# TorpedoSOM_ReceptorS.net
KiCad netlist of a schematic drawn in Altium Designer
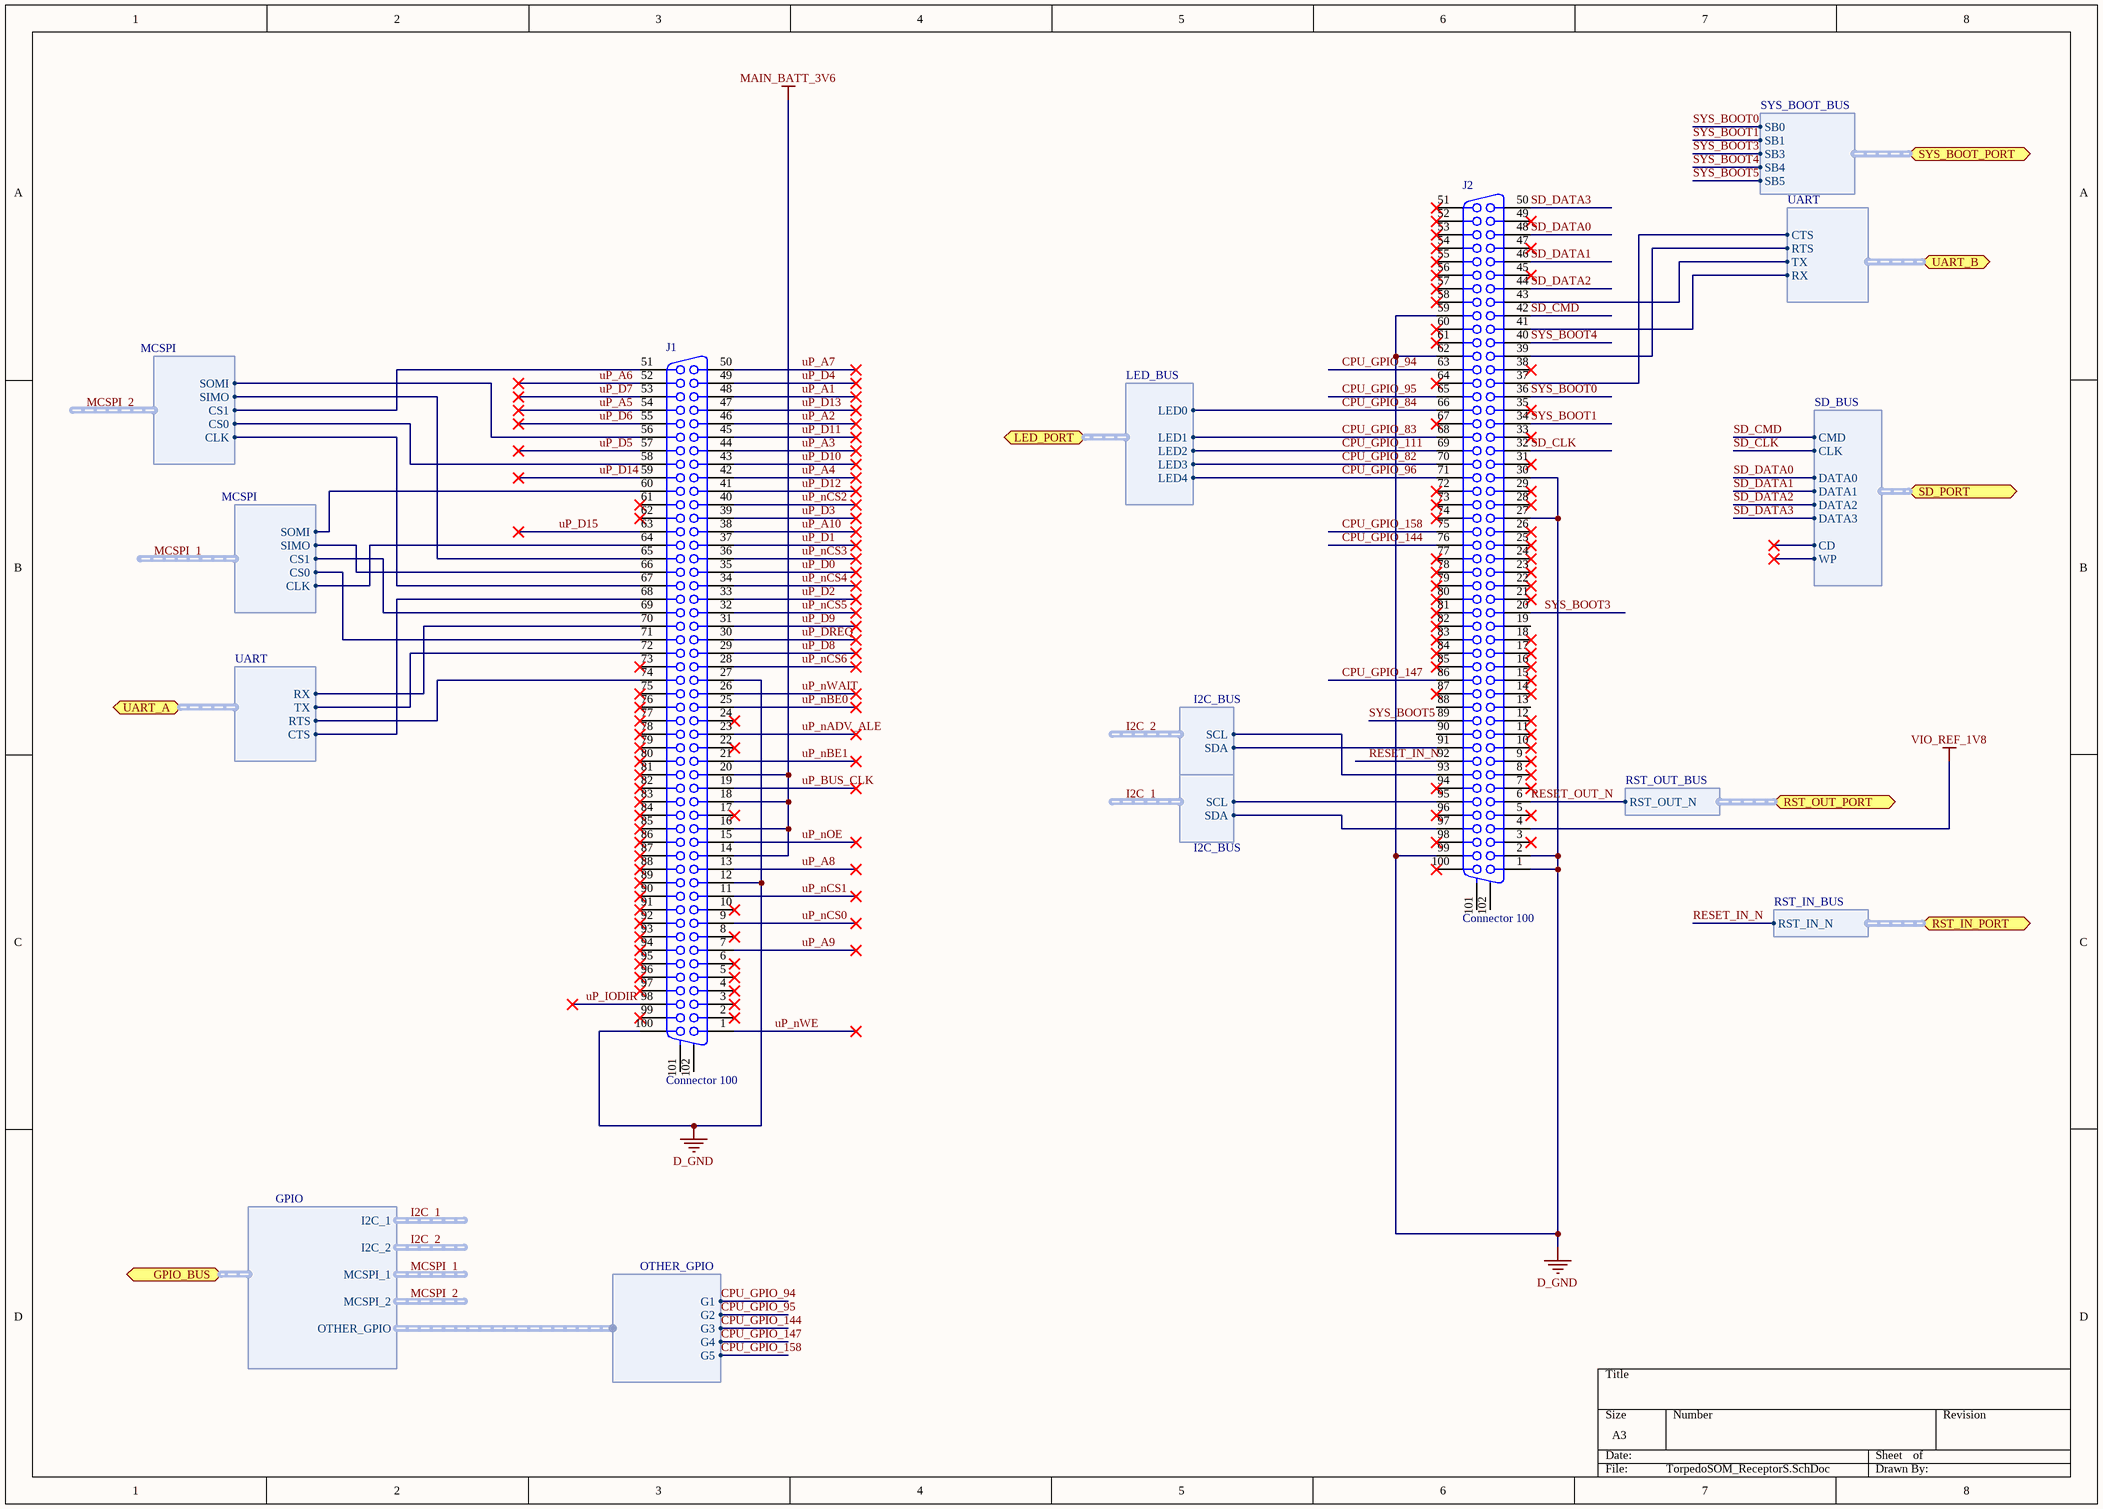
[diagram p0: TorpedoSOM_ReceptorS.SchDoc]

(export (version "E")
  (design (tool "Eeschema 10.0.6"))
  (components
    (comp (ref "J1")
      (value "Connector 100")
      (footprint "SOP127P600-8N_100PinConnRecptr_Hirose:SOP127P600-8N_100PinConnRecptr_Hirose")
      (description "Receptacle Header Assemby")
      (fields (field (name "PUBLISHER") "Altium Limited"))
      (libsource (lib "Miscellaneous Connectors") (part "Connector 100"))
    )
    (comp (ref "J2")
      (value "Connector 100")
      (footprint "SOP127P600-8N_100PinConnRecptr_Hirose:SOP127P600-8N_100PinConnRecptr_Hirose")
      (description "Receptacle Header Assemby")
      (fields (field (name "PUBLISHER") "Altium Limited"))
      (libsource (lib "Miscellaneous Connectors") (part "Connector 100"))
    )
  )
  (nets
    (net (code "17") (name "/CPU_GPIO_82") (class "Default")
      (node (ref "J2") (pin "70") (pinfunction "70_70") (pintype "passive"))
    )
    (net (code "18") (name "/CPU_GPIO_83") (class "Default")
      (node (ref "J2") (pin "68") (pinfunction "68_68") (pintype "passive"))
    )
    (net (code "19") (name "/CPU_GPIO_84") (class "Default")
      (node (ref "J2") (pin "66") (pinfunction "66_66") (pintype "passive"))
    )
    (net (code "20") (name "/CPU_GPIO_94") (class "Default")
      (node (ref "J2") (pin "63") (pinfunction "63_63") (pintype "passive"))
    )
    (net (code "21") (name "/CPU_GPIO_95") (class "Default")
      (node (ref "J2") (pin "65") (pinfunction "65_65") (pintype "passive"))
    )
    (net (code "22") (name "/CPU_GPIO_96") (class "Default")
      (node (ref "J2") (pin "71") (pinfunction "71_71") (pintype "passive"))
    )
    (net (code "23") (name "/CPU_GPIO_111") (class "Default")
      (node (ref "J2") (pin "69") (pinfunction "69_69") (pintype "passive"))
    )
    (net (code "24") (name "/CPU_GPIO_144") (class "Default")
      (node (ref "J2") (pin "76") (pinfunction "76_76") (pintype "passive"))
    )
    (net (code "25") (name "/CPU_GPIO_147") (class "Default")
      (node (ref "J2") (pin "86") (pinfunction "86_86") (pintype "passive"))
    )
    (net (code "26") (name "/CPU_GPIO_158") (class "Default")
      (node (ref "J2") (pin "75") (pinfunction "75_75") (pintype "passive"))
    )
    (net (code "32") (name "/RESET_IN_N") (class "Default")
      (node (ref "J2") (pin "92") (pinfunction "92_92") (pintype "passive"))
    )
    (net (code "33") (name "/RESET_OUT_N") (class "Default")
      (node (ref "J2") (pin "6") (pinfunction "6_6") (pintype "passive"))
    )
    (net (code "34") (name "/SD_CLK") (class "Default")
      (node (ref "J2") (pin "32") (pinfunction "32_32") (pintype "passive"))
    )
    (net (code "35") (name "/SD_CMD") (class "Default")
      (node (ref "J2") (pin "42") (pinfunction "42_42") (pintype "passive"))
    )
    (net (code "36") (name "/SD_DATA0") (class "Default")
      (node (ref "J2") (pin "48") (pinfunction "48_48") (pintype "passive"))
    )
    (net (code "37") (name "/SD_DATA1") (class "Default")
      (node (ref "J2") (pin "46") (pinfunction "46_46") (pintype "passive"))
    )
    (net (code "38") (name "/SD_DATA2") (class "Default")
      (node (ref "J2") (pin "44") (pinfunction "44_44") (pintype "passive"))
    )
    (net (code "39") (name "/SD_DATA3") (class "Default")
      (node (ref "J2") (pin "50") (pinfunction "50_50") (pintype "passive"))
    )
    (net (code "40") (name "/SYS_BOOT0") (class "Default")
      (node (ref "J2") (pin "36") (pinfunction "36_36") (pintype "passive"))
    )
    (net (code "41") (name "/SYS_BOOT1") (class "Default")
      (node (ref "J2") (pin "34") (pinfunction "34_34") (pintype "passive"))
    )
    (net (code "42") (name "/SYS_BOOT3") (class "Default")
      (node (ref "J2") (pin "20") (pinfunction "20_20") (pintype "passive"))
    )
    (net (code "43") (name "/SYS_BOOT4") (class "Default")
      (node (ref "J2") (pin "40") (pinfunction "40_40") (pintype "passive"))
    )
    (net (code "44") (name "/SYS_BOOT5") (class "Default")
      (node (ref "J2") (pin "89") (pinfunction "89_89") (pintype "passive"))
    )
    (net (code "45") (name "/uP_A1") (class "Default")
      (node (ref "J1") (pin "48") (pinfunction "48_48") (pintype "passive+no_connect"))
    )
    (net (code "46") (name "/uP_A2") (class "Default")
      (node (ref "J1") (pin "46") (pinfunction "46_46") (pintype "passive+no_connect"))
    )
    (net (code "47") (name "/uP_A3") (class "Default")
      (node (ref "J1") (pin "44") (pinfunction "44_44") (pintype "passive+no_connect"))
    )
    (net (code "48") (name "/uP_A4") (class "Default")
      (node (ref "J1") (pin "42") (pinfunction "42_42") (pintype "passive+no_connect"))
    )
    (net (code "49") (name "/uP_A5") (class "Default")
      (node (ref "J1") (pin "54") (pinfunction "54_54") (pintype "passive+no_connect"))
    )
    (net (code "50") (name "/uP_A6") (class "Default")
      (node (ref "J1") (pin "52") (pinfunction "52_52") (pintype "passive+no_connect"))
    )
    (net (code "51") (name "/uP_A7") (class "Default")
      (node (ref "J1") (pin "50") (pinfunction "50_50") (pintype "passive+no_connect"))
    )
    (net (code "52") (name "/uP_A8") (class "Default")
      (node (ref "J1") (pin "13") (pinfunction "13_13") (pintype "passive+no_connect"))
    )
    (net (code "53") (name "/uP_A9") (class "Default")
      (node (ref "J1") (pin "7") (pinfunction "7_7") (pintype "passive+no_connect"))
    )
    (net (code "54") (name "/uP_A10") (class "Default")
      (node (ref "J1") (pin "38") (pinfunction "38_38") (pintype "passive+no_connect"))
    )
    (net (code "55") (name "/uP_BUS_CLK") (class "Default")
      (node (ref "J1") (pin "19") (pinfunction "19_19") (pintype "passive+no_connect"))
    )
    (net (code "56") (name "/uP_D0") (class "Default")
      (node (ref "J1") (pin "35") (pinfunction "35_35") (pintype "passive+no_connect"))
    )
    (net (code "57") (name "/uP_D1") (class "Default")
      (node (ref "J1") (pin "37") (pinfunction "37_37") (pintype "passive+no_connect"))
    )
    (net (code "58") (name "/uP_D2") (class "Default")
      (node (ref "J1") (pin "33") (pinfunction "33_33") (pintype "passive+no_connect"))
    )
    (net (code "59") (name "/uP_D3") (class "Default")
      (node (ref "J1") (pin "39") (pinfunction "39_39") (pintype "passive+no_connect"))
    )
    (net (code "60") (name "/uP_D4") (class "Default")
      (node (ref "J1") (pin "49") (pinfunction "49_49") (pintype "passive+no_connect"))
    )
    (net (code "61") (name "/uP_D5") (class "Default")
      (node (ref "J1") (pin "57") (pinfunction "57_57") (pintype "passive+no_connect"))
    )
    (net (code "62") (name "/uP_D6") (class "Default")
      (node (ref "J1") (pin "55") (pinfunction "55_55") (pintype "passive+no_connect"))
    )
    (net (code "63") (name "/uP_D7") (class "Default")
      (node (ref "J1") (pin "53") (pinfunction "53_53") (pintype "passive+no_connect"))
    )
    (net (code "64") (name "/uP_D8") (class "Default")
      (node (ref "J1") (pin "29") (pinfunction "29_29") (pintype "passive+no_connect"))
    )
    (net (code "65") (name "/uP_D9") (class "Default")
      (node (ref "J1") (pin "31") (pinfunction "31_31") (pintype "passive+no_connect"))
    )
    (net (code "66") (name "/uP_D10") (class "Default")
      (node (ref "J1") (pin "43") (pinfunction "43_43") (pintype "passive+no_connect"))
    )
    (net (code "67") (name "/uP_D11") (class "Default")
      (node (ref "J1") (pin "45") (pinfunction "45_45") (pintype "passive+no_connect"))
    )
    (net (code "68") (name "/uP_D12") (class "Default")
      (node (ref "J1") (pin "41") (pinfunction "41_41") (pintype "passive+no_connect"))
    )
    (net (code "69") (name "/uP_D13") (class "Default")
      (node (ref "J1") (pin "47") (pinfunction "47_47") (pintype "passive+no_connect"))
    )
    (net (code "70") (name "/uP_D14") (class "Default")
      (node (ref "J1") (pin "59") (pinfunction "59_59") (pintype "passive+no_connect"))
    )
    (net (code "71") (name "/uP_D15") (class "Default")
      (node (ref "J1") (pin "63") (pinfunction "63_63") (pintype "passive+no_connect"))
    )
    (net (code "72") (name "/uP_DREQ") (class "Default")
      (node (ref "J1") (pin "30") (pinfunction "30_30") (pintype "passive+no_connect"))
    )
    (net (code "73") (name "/uP_IODIR") (class "Default")
      (node (ref "J1") (pin "98") (pinfunction "98_98") (pintype "passive+no_connect"))
    )
    (net (code "74") (name "/uP_nADV_ALE") (class "Default")
      (node (ref "J1") (pin "23") (pinfunction "23_23") (pintype "passive+no_connect"))
    )
    (net (code "75") (name "/uP_nBE0") (class "Default")
      (node (ref "J1") (pin "25") (pinfunction "25_25") (pintype "passive+no_connect"))
    )
    (net (code "76") (name "/uP_nBE1") (class "Default")
      (node (ref "J1") (pin "21") (pinfunction "21_21") (pintype "passive+no_connect"))
    )
    (net (code "77") (name "/uP_nCS0") (class "Default")
      (node (ref "J1") (pin "9") (pinfunction "9_9") (pintype "passive+no_connect"))
    )
    (net (code "78") (name "/uP_nCS1") (class "Default")
      (node (ref "J1") (pin "11") (pinfunction "11_11") (pintype "passive+no_connect"))
    )
    (net (code "79") (name "/uP_nCS2") (class "Default")
      (node (ref "J1") (pin "40") (pinfunction "40_40") (pintype "passive+no_connect"))
    )
    (net (code "80") (name "/uP_nCS3") (class "Default")
      (node (ref "J1") (pin "36") (pinfunction "36_36") (pintype "passive+no_connect"))
    )
    (net (code "81") (name "/uP_nCS4") (class "Default")
      (node (ref "J1") (pin "34") (pinfunction "34_34") (pintype "passive+no_connect"))
    )
    (net (code "82") (name "/uP_nCS5") (class "Default")
      (node (ref "J1") (pin "32") (pinfunction "32_32") (pintype "passive+no_connect"))
    )
    (net (code "83") (name "/uP_nCS6") (class "Default")
      (node (ref "J1") (pin "28") (pinfunction "28_28") (pintype "passive+no_connect"))
    )
    (net (code "84") (name "/uP_nOE") (class "Default")
      (node (ref "J1") (pin "15") (pinfunction "15_15") (pintype "passive+no_connect"))
    )
    (net (code "85") (name "/uP_nWAIT") (class "Default")
      (node (ref "J1") (pin "26") (pinfunction "26_26") (pintype "passive+no_connect"))
    )
    (net (code "86") (name "/uP_nWE") (class "Default")
      (node (ref "J1") (pin "1") (pinfunction "1_1") (pintype "passive+no_connect"))
    )
    (net (code "98") (name "D_GND") (class "Default")
      (node (ref "J1") (pin "100") (pinfunction "100_100") (pintype "passive"))
      (node (ref "J1") (pin "12") (pinfunction "12_12") (pintype "passive"))
      (node (ref "J1") (pin "27") (pinfunction "27_27") (pintype "passive"))
      (node (ref "J2") (pin "1") (pinfunction "1_1") (pintype "passive"))
      (node (ref "J2") (pin "2") (pinfunction "2_2") (pintype "passive"))
      (node (ref "J2") (pin "27") (pinfunction "27_27") (pintype "passive"))
      (node (ref "J2") (pin "30") (pinfunction "30_30") (pintype "passive"))
      (node (ref "J2") (pin "59") (pinfunction "59_59") (pintype "passive"))
      (node (ref "J2") (pin "62") (pinfunction "62_62") (pintype "passive"))
      (node (ref "J2") (pin "99") (pinfunction "99_99") (pintype "passive"))
    )
    (net (code "99") (name "MAIN_BATT_3V6") (class "Default")
      (node (ref "J1") (pin "14") (pinfunction "14_14") (pintype "passive"))
      (node (ref "J1") (pin "16") (pinfunction "16_16") (pintype "passive"))
      (node (ref "J1") (pin "18") (pinfunction "18_18") (pintype "passive"))
      (node (ref "J1") (pin "20") (pinfunction "20_20") (pintype "passive"))
    )
    (net (code "100") (name "VIO_REF_1V8") (class "Default")
      (node (ref "J2") (pin "4") (pinfunction "4_4") (pintype "passive"))
    )
    (net (code "101") (name "unconnected-(J1-MH1-Pad101)") (class "Default")
      (node (ref "J1") (pin "101") (pinfunction "MH1_101") (pintype "passive"))
    )
    (net (code "102") (name "unconnected-(J1-MH2-Pad102)") (class "Default")
      (node (ref "J1") (pin "102") (pinfunction "MH2_102") (pintype "passive"))
    )
    (net (code "103") (name "unconnected-(J1-Pad2)") (class "Default")
      (node (ref "J1") (pin "2") (pinfunction "2_2") (pintype "passive+no_connect"))
    )
    (net (code "104") (name "unconnected-(J1-Pad3)") (class "Default")
      (node (ref "J1") (pin "3") (pinfunction "3_3") (pintype "passive+no_connect"))
    )
    (net (code "105") (name "unconnected-(J1-Pad4)") (class "Default")
      (node (ref "J1") (pin "4") (pinfunction "4_4") (pintype "passive+no_connect"))
    )
    (net (code "106") (name "unconnected-(J1-Pad5)") (class "Default")
      (node (ref "J1") (pin "5") (pinfunction "5_5") (pintype "passive+no_connect"))
    )
    (net (code "107") (name "unconnected-(J1-Pad6)") (class "Default")
      (node (ref "J1") (pin "6") (pinfunction "6_6") (pintype "passive+no_connect"))
    )
    (net (code "108") (name "unconnected-(J1-Pad8)") (class "Default")
      (node (ref "J1") (pin "8") (pinfunction "8_8") (pintype "passive+no_connect"))
    )
    (net (code "109") (name "unconnected-(J1-Pad10)") (class "Default")
      (node (ref "J1") (pin "10") (pinfunction "10_10") (pintype "passive+no_connect"))
    )
    (net (code "110") (name "unconnected-(J1-Pad17)") (class "Default")
      (node (ref "J1") (pin "17") (pinfunction "17_17") (pintype "passive+no_connect"))
    )
    (net (code "111") (name "unconnected-(J1-Pad22)") (class "Default")
      (node (ref "J1") (pin "22") (pinfunction "22_22") (pintype "passive+no_connect"))
    )
    (net (code "112") (name "unconnected-(J1-Pad24)") (class "Default")
      (node (ref "J1") (pin "24") (pinfunction "24_24") (pintype "passive+no_connect"))
    )
    (net (code "113") (name "unconnected-(J1-Pad51)") (class "Default")
      (node (ref "J1") (pin "51") (pinfunction "51_51") (pintype "passive"))
    )
    (net (code "114") (name "unconnected-(J1-Pad56)") (class "Default")
      (node (ref "J1") (pin "56") (pinfunction "56_56") (pintype "passive"))
    )
    (net (code "115") (name "unconnected-(J1-Pad58)") (class "Default")
      (node (ref "J1") (pin "58") (pinfunction "58_58") (pintype "passive"))
    )
    (net (code "116") (name "unconnected-(J1-Pad60)") (class "Default")
      (node (ref "J1") (pin "60") (pinfunction "60_60") (pintype "passive"))
    )
    (net (code "117") (name "unconnected-(J1-Pad61)") (class "Default")
      (node (ref "J1") (pin "61") (pinfunction "61_61") (pintype "passive+no_connect"))
    )
    (net (code "118") (name "unconnected-(J1-Pad62)") (class "Default")
      (node (ref "J1") (pin "62") (pinfunction "62_62") (pintype "passive+no_connect"))
    )
    (net (code "119") (name "unconnected-(J1-Pad64)") (class "Default")
      (node (ref "J1") (pin "64") (pinfunction "64_64") (pintype "passive"))
    )
    (net (code "120") (name "unconnected-(J1-Pad65)") (class "Default")
      (node (ref "J1") (pin "65") (pinfunction "65_65") (pintype "passive"))
    )
    (net (code "121") (name "unconnected-(J1-Pad66)") (class "Default")
      (node (ref "J1") (pin "66") (pinfunction "66_66") (pintype "passive"))
    )
    (net (code "122") (name "unconnected-(J1-Pad67)") (class "Default")
      (node (ref "J1") (pin "67") (pinfunction "67_67") (pintype "passive"))
    )
    (net (code "123") (name "unconnected-(J1-Pad68)") (class "Default")
      (node (ref "J1") (pin "68") (pinfunction "68_68") (pintype "passive"))
    )
    (net (code "124") (name "unconnected-(J1-Pad69)") (class "Default")
      (node (ref "J1") (pin "69") (pinfunction "69_69") (pintype "passive"))
    )
    (net (code "125") (name "unconnected-(J1-Pad70)") (class "Default")
      (node (ref "J1") (pin "70") (pinfunction "70_70") (pintype "passive"))
    )
    (net (code "126") (name "unconnected-(J1-Pad71)") (class "Default")
      (node (ref "J1") (pin "71") (pinfunction "71_71") (pintype "passive"))
    )
    (net (code "127") (name "unconnected-(J1-Pad72)") (class "Default")
      (node (ref "J1") (pin "72") (pinfunction "72_72") (pintype "passive"))
    )
    (net (code "128") (name "unconnected-(J1-Pad73)") (class "Default")
      (node (ref "J1") (pin "73") (pinfunction "73_73") (pintype "passive+no_connect"))
    )
    (net (code "129") (name "unconnected-(J1-Pad74)") (class "Default")
      (node (ref "J1") (pin "74") (pinfunction "74_74") (pintype "passive"))
    )
    (net (code "130") (name "unconnected-(J1-Pad75)") (class "Default")
      (node (ref "J1") (pin "75") (pinfunction "75_75") (pintype "passive+no_connect"))
    )
    (net (code "131") (name "unconnected-(J1-Pad76)") (class "Default")
      (node (ref "J1") (pin "76") (pinfunction "76_76") (pintype "passive+no_connect"))
    )
    (net (code "132") (name "unconnected-(J1-Pad77)") (class "Default")
      (node (ref "J1") (pin "77") (pinfunction "77_77") (pintype "passive+no_connect"))
    )
    (net (code "133") (name "unconnected-(J1-Pad78)") (class "Default")
      (node (ref "J1") (pin "78") (pinfunction "78_78") (pintype "passive+no_connect"))
    )
    (net (code "134") (name "unconnected-(J1-Pad79)") (class "Default")
      (node (ref "J1") (pin "79") (pinfunction "79_79") (pintype "passive+no_connect"))
    )
    (net (code "135") (name "unconnected-(J1-Pad80)") (class "Default")
      (node (ref "J1") (pin "80") (pinfunction "80_80") (pintype "passive+no_connect"))
    )
    (net (code "136") (name "unconnected-(J1-Pad81)") (class "Default")
      (node (ref "J1") (pin "81") (pinfunction "81_81") (pintype "passive+no_connect"))
    )
    (net (code "137") (name "unconnected-(J1-Pad82)") (class "Default")
      (node (ref "J1") (pin "82") (pinfunction "82_82") (pintype "passive+no_connect"))
    )
    (net (code "138") (name "unconnected-(J1-Pad83)") (class "Default")
      (node (ref "J1") (pin "83") (pinfunction "83_83") (pintype "passive+no_connect"))
    )
    (net (code "139") (name "unconnected-(J1-Pad84)") (class "Default")
      (node (ref "J1") (pin "84") (pinfunction "84_84") (pintype "passive+no_connect"))
    )
    (net (code "140") (name "unconnected-(J1-Pad85)") (class "Default")
      (node (ref "J1") (pin "85") (pinfunction "85_85") (pintype "passive+no_connect"))
    )
    (net (code "141") (name "unconnected-(J1-Pad86)") (class "Default")
      (node (ref "J1") (pin "86") (pinfunction "86_86") (pintype "passive+no_connect"))
    )
    (net (code "142") (name "unconnected-(J1-Pad87)") (class "Default")
      (node (ref "J1") (pin "87") (pinfunction "87_87") (pintype "passive+no_connect"))
    )
    (net (code "143") (name "unconnected-(J1-Pad88)") (class "Default")
      (node (ref "J1") (pin "88") (pinfunction "88_88") (pintype "passive+no_connect"))
    )
    (net (code "144") (name "unconnected-(J1-Pad89)") (class "Default")
      (node (ref "J1") (pin "89") (pinfunction "89_89") (pintype "passive+no_connect"))
    )
    (net (code "145") (name "unconnected-(J1-Pad90)") (class "Default")
      (node (ref "J1") (pin "90") (pinfunction "90_90") (pintype "passive+no_connect"))
    )
    (net (code "146") (name "unconnected-(J1-Pad91)") (class "Default")
      (node (ref "J1") (pin "91") (pinfunction "91_91") (pintype "passive+no_connect"))
    )
    (net (code "147") (name "unconnected-(J1-Pad92)") (class "Default")
      (node (ref "J1") (pin "92") (pinfunction "92_92") (pintype "passive+no_connect"))
    )
    (net (code "148") (name "unconnected-(J1-Pad93)") (class "Default")
      (node (ref "J1") (pin "93") (pinfunction "93_93") (pintype "passive+no_connect"))
    )
    (net (code "149") (name "unconnected-(J1-Pad94)") (class "Default")
      (node (ref "J1") (pin "94") (pinfunction "94_94") (pintype "passive+no_connect"))
    )
    (net (code "150") (name "unconnected-(J1-Pad95)") (class "Default")
      (node (ref "J1") (pin "95") (pinfunction "95_95") (pintype "passive+no_connect"))
    )
    (net (code "151") (name "unconnected-(J1-Pad96)") (class "Default")
      (node (ref "J1") (pin "96") (pinfunction "96_96") (pintype "passive+no_connect"))
    )
    (net (code "152") (name "unconnected-(J1-Pad97)") (class "Default")
      (node (ref "J1") (pin "97") (pinfunction "97_97") (pintype "passive+no_connect"))
    )
    (net (code "153") (name "unconnected-(J1-Pad99)") (class "Default")
      (node (ref "J1") (pin "99") (pinfunction "99_99") (pintype "passive+no_connect"))
    )
    (net (code "154") (name "unconnected-(J2-MH1-Pad101)") (class "Default")
      (node (ref "J2") (pin "101") (pinfunction "MH1_101") (pintype "passive"))
    )
    (net (code "155") (name "unconnected-(J2-MH2-Pad102)") (class "Default")
      (node (ref "J2") (pin "102") (pinfunction "MH2_102") (pintype "passive"))
    )
    (net (code "156") (name "unconnected-(J2-Pad3)") (class "Default")
      (node (ref "J2") (pin "3") (pinfunction "3_3") (pintype "passive+no_connect"))
    )
    (net (code "157") (name "unconnected-(J2-Pad5)") (class "Default")
      (node (ref "J2") (pin "5") (pinfunction "5_5") (pintype "passive+no_connect"))
    )
    (net (code "158") (name "unconnected-(J2-Pad7)") (class "Default")
      (node (ref "J2") (pin "7") (pinfunction "7_7") (pintype "passive+no_connect"))
    )
    (net (code "159") (name "unconnected-(J2-Pad8)") (class "Default")
      (node (ref "J2") (pin "8") (pinfunction "8_8") (pintype "passive+no_connect"))
    )
    (net (code "160") (name "unconnected-(J2-Pad9)") (class "Default")
      (node (ref "J2") (pin "9") (pinfunction "9_9") (pintype "passive+no_connect"))
    )
    (net (code "161") (name "unconnected-(J2-Pad10)") (class "Default")
      (node (ref "J2") (pin "10") (pinfunction "10_10") (pintype "passive+no_connect"))
    )
    (net (code "162") (name "unconnected-(J2-Pad11)") (class "Default")
      (node (ref "J2") (pin "11") (pinfunction "11_11") (pintype "passive+no_connect"))
    )
    (net (code "163") (name "unconnected-(J2-Pad12)") (class "Default")
      (node (ref "J2") (pin "12") (pinfunction "12_12") (pintype "passive+no_connect"))
    )
    (net (code "164") (name "unconnected-(J2-Pad13)") (class "Default")
      (node (ref "J2") (pin "13") (pinfunction "13_13") (pintype "passive"))
    )
    (net (code "165") (name "unconnected-(J2-Pad14)") (class "Default")
      (node (ref "J2") (pin "14") (pinfunction "14_14") (pintype "passive+no_connect"))
    )
    (net (code "166") (name "unconnected-(J2-Pad15)") (class "Default")
      (node (ref "J2") (pin "15") (pinfunction "15_15") (pintype "passive+no_connect"))
    )
    (net (code "167") (name "unconnected-(J2-Pad16)") (class "Default")
      (node (ref "J2") (pin "16") (pinfunction "16_16") (pintype "passive+no_connect"))
    )
    (net (code "168") (name "unconnected-(J2-Pad17)") (class "Default")
      (node (ref "J2") (pin "17") (pinfunction "17_17") (pintype "passive+no_connect"))
    )
    (net (code "169") (name "unconnected-(J2-Pad18)") (class "Default")
      (node (ref "J2") (pin "18") (pinfunction "18_18") (pintype "passive+no_connect"))
    )
    (net (code "170") (name "unconnected-(J2-Pad19)") (class "Default")
      (node (ref "J2") (pin "19") (pinfunction "19_19") (pintype "passive"))
    )
    (net (code "171") (name "unconnected-(J2-Pad21)") (class "Default")
      (node (ref "J2") (pin "21") (pinfunction "21_21") (pintype "passive+no_connect"))
    )
    (net (code "172") (name "unconnected-(J2-Pad22)") (class "Default")
      (node (ref "J2") (pin "22") (pinfunction "22_22") (pintype "passive+no_connect"))
    )
    (net (code "173") (name "unconnected-(J2-Pad23)") (class "Default")
      (node (ref "J2") (pin "23") (pinfunction "23_23") (pintype "passive+no_connect"))
    )
    (net (code "174") (name "unconnected-(J2-Pad24)") (class "Default")
      (node (ref "J2") (pin "24") (pinfunction "24_24") (pintype "passive+no_connect"))
    )
    (net (code "175") (name "unconnected-(J2-Pad25)") (class "Default")
      (node (ref "J2") (pin "25") (pinfunction "25_25") (pintype "passive+no_connect"))
    )
    (net (code "176") (name "unconnected-(J2-Pad26)") (class "Default")
      (node (ref "J2") (pin "26") (pinfunction "26_26") (pintype "passive+no_connect"))
    )
    (net (code "177") (name "unconnected-(J2-Pad28)") (class "Default")
      (node (ref "J2") (pin "28") (pinfunction "28_28") (pintype "passive+no_connect"))
    )
    (net (code "178") (name "unconnected-(J2-Pad29)") (class "Default")
      (node (ref "J2") (pin "29") (pinfunction "29_29") (pintype "passive+no_connect"))
    )
    (net (code "179") (name "unconnected-(J2-Pad31)") (class "Default")
      (node (ref "J2") (pin "31") (pinfunction "31_31") (pintype "passive+no_connect"))
    )
    (net (code "180") (name "unconnected-(J2-Pad33)") (class "Default")
      (node (ref "J2") (pin "33") (pinfunction "33_33") (pintype "passive+no_connect"))
    )
    (net (code "181") (name "unconnected-(J2-Pad35)") (class "Default")
      (node (ref "J2") (pin "35") (pinfunction "35_35") (pintype "passive+no_connect"))
    )
    (net (code "182") (name "unconnected-(J2-Pad37)") (class "Default")
      (node (ref "J2") (pin "37") (pinfunction "37_37") (pintype "passive"))
    )
    (net (code "183") (name "unconnected-(J2-Pad38)") (class "Default")
      (node (ref "J2") (pin "38") (pinfunction "38_38") (pintype "passive+no_connect"))
    )
    (net (code "184") (name "unconnected-(J2-Pad39)") (class "Default")
      (node (ref "J2") (pin "39") (pinfunction "39_39") (pintype "passive"))
    )
    (net (code "185") (name "unconnected-(J2-Pad41)") (class "Default")
      (node (ref "J2") (pin "41") (pinfunction "41_41") (pintype "passive"))
    )
    (net (code "186") (name "unconnected-(J2-Pad43)") (class "Default")
      (node (ref "J2") (pin "43") (pinfunction "43_43") (pintype "passive"))
    )
    (net (code "187") (name "unconnected-(J2-Pad45)") (class "Default")
      (node (ref "J2") (pin "45") (pinfunction "45_45") (pintype "passive+no_connect"))
    )
    (net (code "188") (name "unconnected-(J2-Pad47)") (class "Default")
      (node (ref "J2") (pin "47") (pinfunction "47_47") (pintype "passive+no_connect"))
    )
    (net (code "189") (name "unconnected-(J2-Pad49)") (class "Default")
      (node (ref "J2") (pin "49") (pinfunction "49_49") (pintype "passive+no_connect"))
    )
    (net (code "190") (name "unconnected-(J2-Pad51)") (class "Default")
      (node (ref "J2") (pin "51") (pinfunction "51_51") (pintype "passive+no_connect"))
    )
    (net (code "191") (name "unconnected-(J2-Pad52)") (class "Default")
      (node (ref "J2") (pin "52") (pinfunction "52_52") (pintype "passive+no_connect"))
    )
    (net (code "192") (name "unconnected-(J2-Pad53)") (class "Default")
      (node (ref "J2") (pin "53") (pinfunction "53_53") (pintype "passive+no_connect"))
    )
    (net (code "193") (name "unconnected-(J2-Pad54)") (class "Default")
      (node (ref "J2") (pin "54") (pinfunction "54_54") (pintype "passive+no_connect"))
    )
    (net (code "194") (name "unconnected-(J2-Pad55)") (class "Default")
      (node (ref "J2") (pin "55") (pinfunction "55_55") (pintype "passive+no_connect"))
    )
    (net (code "195") (name "unconnected-(J2-Pad56)") (class "Default")
      (node (ref "J2") (pin "56") (pinfunction "56_56") (pintype "passive+no_connect"))
    )
    (net (code "196") (name "unconnected-(J2-Pad57)") (class "Default")
      (node (ref "J2") (pin "57") (pinfunction "57_57") (pintype "passive+no_connect"))
    )
    (net (code "197") (name "unconnected-(J2-Pad58)") (class "Default")
      (node (ref "J2") (pin "58") (pinfunction "58_58") (pintype "passive+no_connect"))
    )
    (net (code "198") (name "unconnected-(J2-Pad60)") (class "Default")
      (node (ref "J2") (pin "60") (pinfunction "60_60") (pintype "passive+no_connect"))
    )
    (net (code "199") (name "unconnected-(J2-Pad61)") (class "Default")
      (node (ref "J2") (pin "61") (pinfunction "61_61") (pintype "passive+no_connect"))
    )
    (net (code "200") (name "unconnected-(J2-Pad64)") (class "Default")
      (node (ref "J2") (pin "64") (pinfunction "64_64") (pintype "passive+no_connect"))
    )
    (net (code "201") (name "unconnected-(J2-Pad67)") (class "Default")
      (node (ref "J2") (pin "67") (pinfunction "67_67") (pintype "passive+no_connect"))
    )
    (net (code "202") (name "unconnected-(J2-Pad72)") (class "Default")
      (node (ref "J2") (pin "72") (pinfunction "72_72") (pintype "passive+no_connect"))
    )
    (net (code "203") (name "unconnected-(J2-Pad73)") (class "Default")
      (node (ref "J2") (pin "73") (pinfunction "73_73") (pintype "passive+no_connect"))
    )
    (net (code "204") (name "unconnected-(J2-Pad74)") (class "Default")
      (node (ref "J2") (pin "74") (pinfunction "74_74") (pintype "passive+no_connect"))
    )
    (net (code "205") (name "unconnected-(J2-Pad77)") (class "Default")
      (node (ref "J2") (pin "77") (pinfunction "77_77") (pintype "passive+no_connect"))
    )
    (net (code "206") (name "unconnected-(J2-Pad78)") (class "Default")
      (node (ref "J2") (pin "78") (pinfunction "78_78") (pintype "passive+no_connect"))
    )
    (net (code "207") (name "unconnected-(J2-Pad79)") (class "Default")
      (node (ref "J2") (pin "79") (pinfunction "79_79") (pintype "passive+no_connect"))
    )
    (net (code "208") (name "unconnected-(J2-Pad80)") (class "Default")
      (node (ref "J2") (pin "80") (pinfunction "80_80") (pintype "passive+no_connect"))
    )
    (net (code "209") (name "unconnected-(J2-Pad81)") (class "Default")
      (node (ref "J2") (pin "81") (pinfunction "81_81") (pintype "passive+no_connect"))
    )
    (net (code "210") (name "unconnected-(J2-Pad82)") (class "Default")
      (node (ref "J2") (pin "82") (pinfunction "82_82") (pintype "passive+no_connect"))
    )
    (net (code "211") (name "unconnected-(J2-Pad83)") (class "Default")
      (node (ref "J2") (pin "83") (pinfunction "83_83") (pintype "passive+no_connect"))
    )
    (net (code "212") (name "unconnected-(J2-Pad84)") (class "Default")
      (node (ref "J2") (pin "84") (pinfunction "84_84") (pintype "passive+no_connect"))
    )
    (net (code "213") (name "unconnected-(J2-Pad85)") (class "Default")
      (node (ref "J2") (pin "85") (pinfunction "85_85") (pintype "passive+no_connect"))
    )
    (net (code "214") (name "unconnected-(J2-Pad87)") (class "Default")
      (node (ref "J2") (pin "87") (pinfunction "87_87") (pintype "passive+no_connect"))
    )
    (net (code "215") (name "unconnected-(J2-Pad88)") (class "Default")
      (node (ref "J2") (pin "88") (pinfunction "88_88") (pintype "passive"))
    )
    (net (code "216") (name "unconnected-(J2-Pad90)") (class "Default")
      (node (ref "J2") (pin "90") (pinfunction "90_90") (pintype "passive"))
    )
    (net (code "217") (name "unconnected-(J2-Pad91)") (class "Default")
      (node (ref "J2") (pin "91") (pinfunction "91_91") (pintype "passive"))
    )
    (net (code "218") (name "unconnected-(J2-Pad93)") (class "Default")
      (node (ref "J2") (pin "93") (pinfunction "93_93") (pintype "passive"))
    )
    (net (code "219") (name "unconnected-(J2-Pad94)") (class "Default")
      (node (ref "J2") (pin "94") (pinfunction "94_94") (pintype "passive+no_connect"))
    )
    (net (code "220") (name "unconnected-(J2-Pad95)") (class "Default")
      (node (ref "J2") (pin "95") (pinfunction "95_95") (pintype "passive"))
    )
    (net (code "221") (name "unconnected-(J2-Pad96)") (class "Default")
      (node (ref "J2") (pin "96") (pinfunction "96_96") (pintype "passive+no_connect"))
    )
    (net (code "222") (name "unconnected-(J2-Pad97)") (class "Default")
      (node (ref "J2") (pin "97") (pinfunction "97_97") (pintype "passive"))
    )
    (net (code "223") (name "unconnected-(J2-Pad98)") (class "Default")
      (node (ref "J2") (pin "98") (pinfunction "98_98") (pintype "passive+no_connect"))
    )
    (net (code "224") (name "unconnected-(J2-Pad100)") (class "Default")
      (node (ref "J2") (pin "100") (pinfunction "100_100") (pintype "passive+no_connect"))
    )
  )
)
